# SATA.net
KiCad netlist of a schematic drawn in Altium Designer
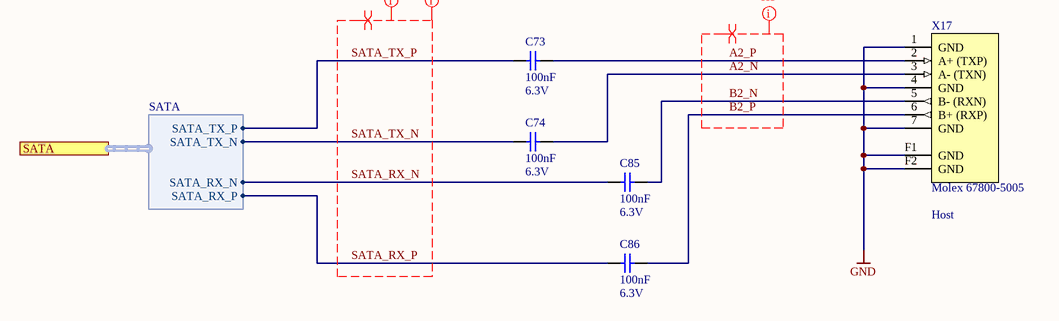
[diagram p0: SATA.schdoc]

(export (version "E")
  (design (tool "Eeschema 10.0.6"))
  (components
    (comp (ref "C73")
      (value "100nF")
      (footprint "CAPC0603X33N_V")
      (description "KON 100nF 6.3V X5R 10% SMD BF 0603 (0201)")
      (fields (field (name "VOLTAGE") "6.3V") (field (name "TOLERANCE") "10%"))
      (libsource (lib "TE") (part "CAP-NP"))
    )
    (comp (ref "C74")
      (value "100nF")
      (footprint "CAPC0603X33N_V")
      (description "KON 100nF 6.3V X5R 10% SMD BF 0603 (0201)")
      (fields (field (name "VOLTAGE") "6.3V") (field (name "TOLERANCE") "10%"))
      (libsource (lib "TE") (part "CAP-NP"))
    )
    (comp (ref "C85")
      (value "100nF")
      (footprint "CAPC0603X33N_V")
      (description "KON 100nF 6.3V X5R 10% SMD BF 0603 (0201)")
      (fields (field (name "VOLTAGE") "6.3V") (field (name "TOLERANCE") "10%"))
      (libsource (lib "TE") (part "CAP-NP"))
    )
    (comp (ref "C86")
      (value "100nF")
      (footprint "CAPC0603X33N_V")
      (description "KON 100nF 6.3V X5R 10% SMD BF 0603 (0201)")
      (fields (field (name "VOLTAGE") "6.3V") (field (name "TOLERANCE") "10%"))
      (libsource (lib "TE") (part "CAP-NP"))
    )
    (comp (ref "X17")
      (value "Molex 67800-5005")
      (footprint "67800-5005")
      (description "SATA 7Pol. Connector Vertical")
      (libsource (lib "TE") (part "SATA"))
    )
  )
  (nets
    (net (code "2") (name "/A2_N") (class "Default")
      (node (ref "C74") (pin "2") (pinfunction "2_2") (pintype "passive"))
      (node (ref "X17") (pin "3") (pinfunction "A-_(TXN)_3") (pintype "input"))
    )
    (net (code "3") (name "/A2_P") (class "Default")
      (node (ref "C73") (pin "2") (pinfunction "2_2") (pintype "passive"))
      (node (ref "X17") (pin "2") (pinfunction "A+_(TXP)_2") (pintype "input"))
    )
    (net (code "4") (name "/B2_N") (class "Default")
      (node (ref "C85") (pin "2") (pinfunction "2_2") (pintype "passive"))
      (node (ref "X17") (pin "5") (pinfunction "B-_(RXN)_5") (pintype "output"))
    )
    (net (code "5") (name "/B2_P") (class "Default")
      (node (ref "C86") (pin "2") (pinfunction "2_2") (pintype "passive"))
      (node (ref "X17") (pin "6") (pinfunction "B+_(RXP)_6") (pintype "output"))
    )
    (net (code "6") (name "/SATA_RX_N") (class "Default")
      (node (ref "C85") (pin "1") (pinfunction "1_1") (pintype "passive"))
    )
    (net (code "7") (name "/SATA_RX_P") (class "Default")
      (node (ref "C86") (pin "1") (pinfunction "1_1") (pintype "passive"))
    )
    (net (code "8") (name "/SATA_TX_N") (class "Default")
      (node (ref "C74") (pin "1") (pinfunction "1_1") (pintype "passive"))
    )
    (net (code "9") (name "/SATA_TX_P") (class "Default")
      (node (ref "C73") (pin "1") (pinfunction "1_1") (pintype "passive"))
    )
    (net (code "11") (name "GND") (class "Default")
      (node (ref "X17") (pin "1") (pinfunction "GND_1") (pintype "power_in"))
      (node (ref "X17") (pin "4") (pinfunction "GND_4") (pintype "power_in"))
      (node (ref "X17") (pin "7") (pinfunction "GND_7") (pintype "power_in"))
      (node (ref "X17") (pin "F1") (pinfunction "GND_F1") (pintype "power_in"))
      (node (ref "X17") (pin "F2") (pinfunction "GND_F2") (pintype "power_in"))
    )
  )
)
